# vco1_pots.net
KiCad netlist of a schematic drawn in EAGLE
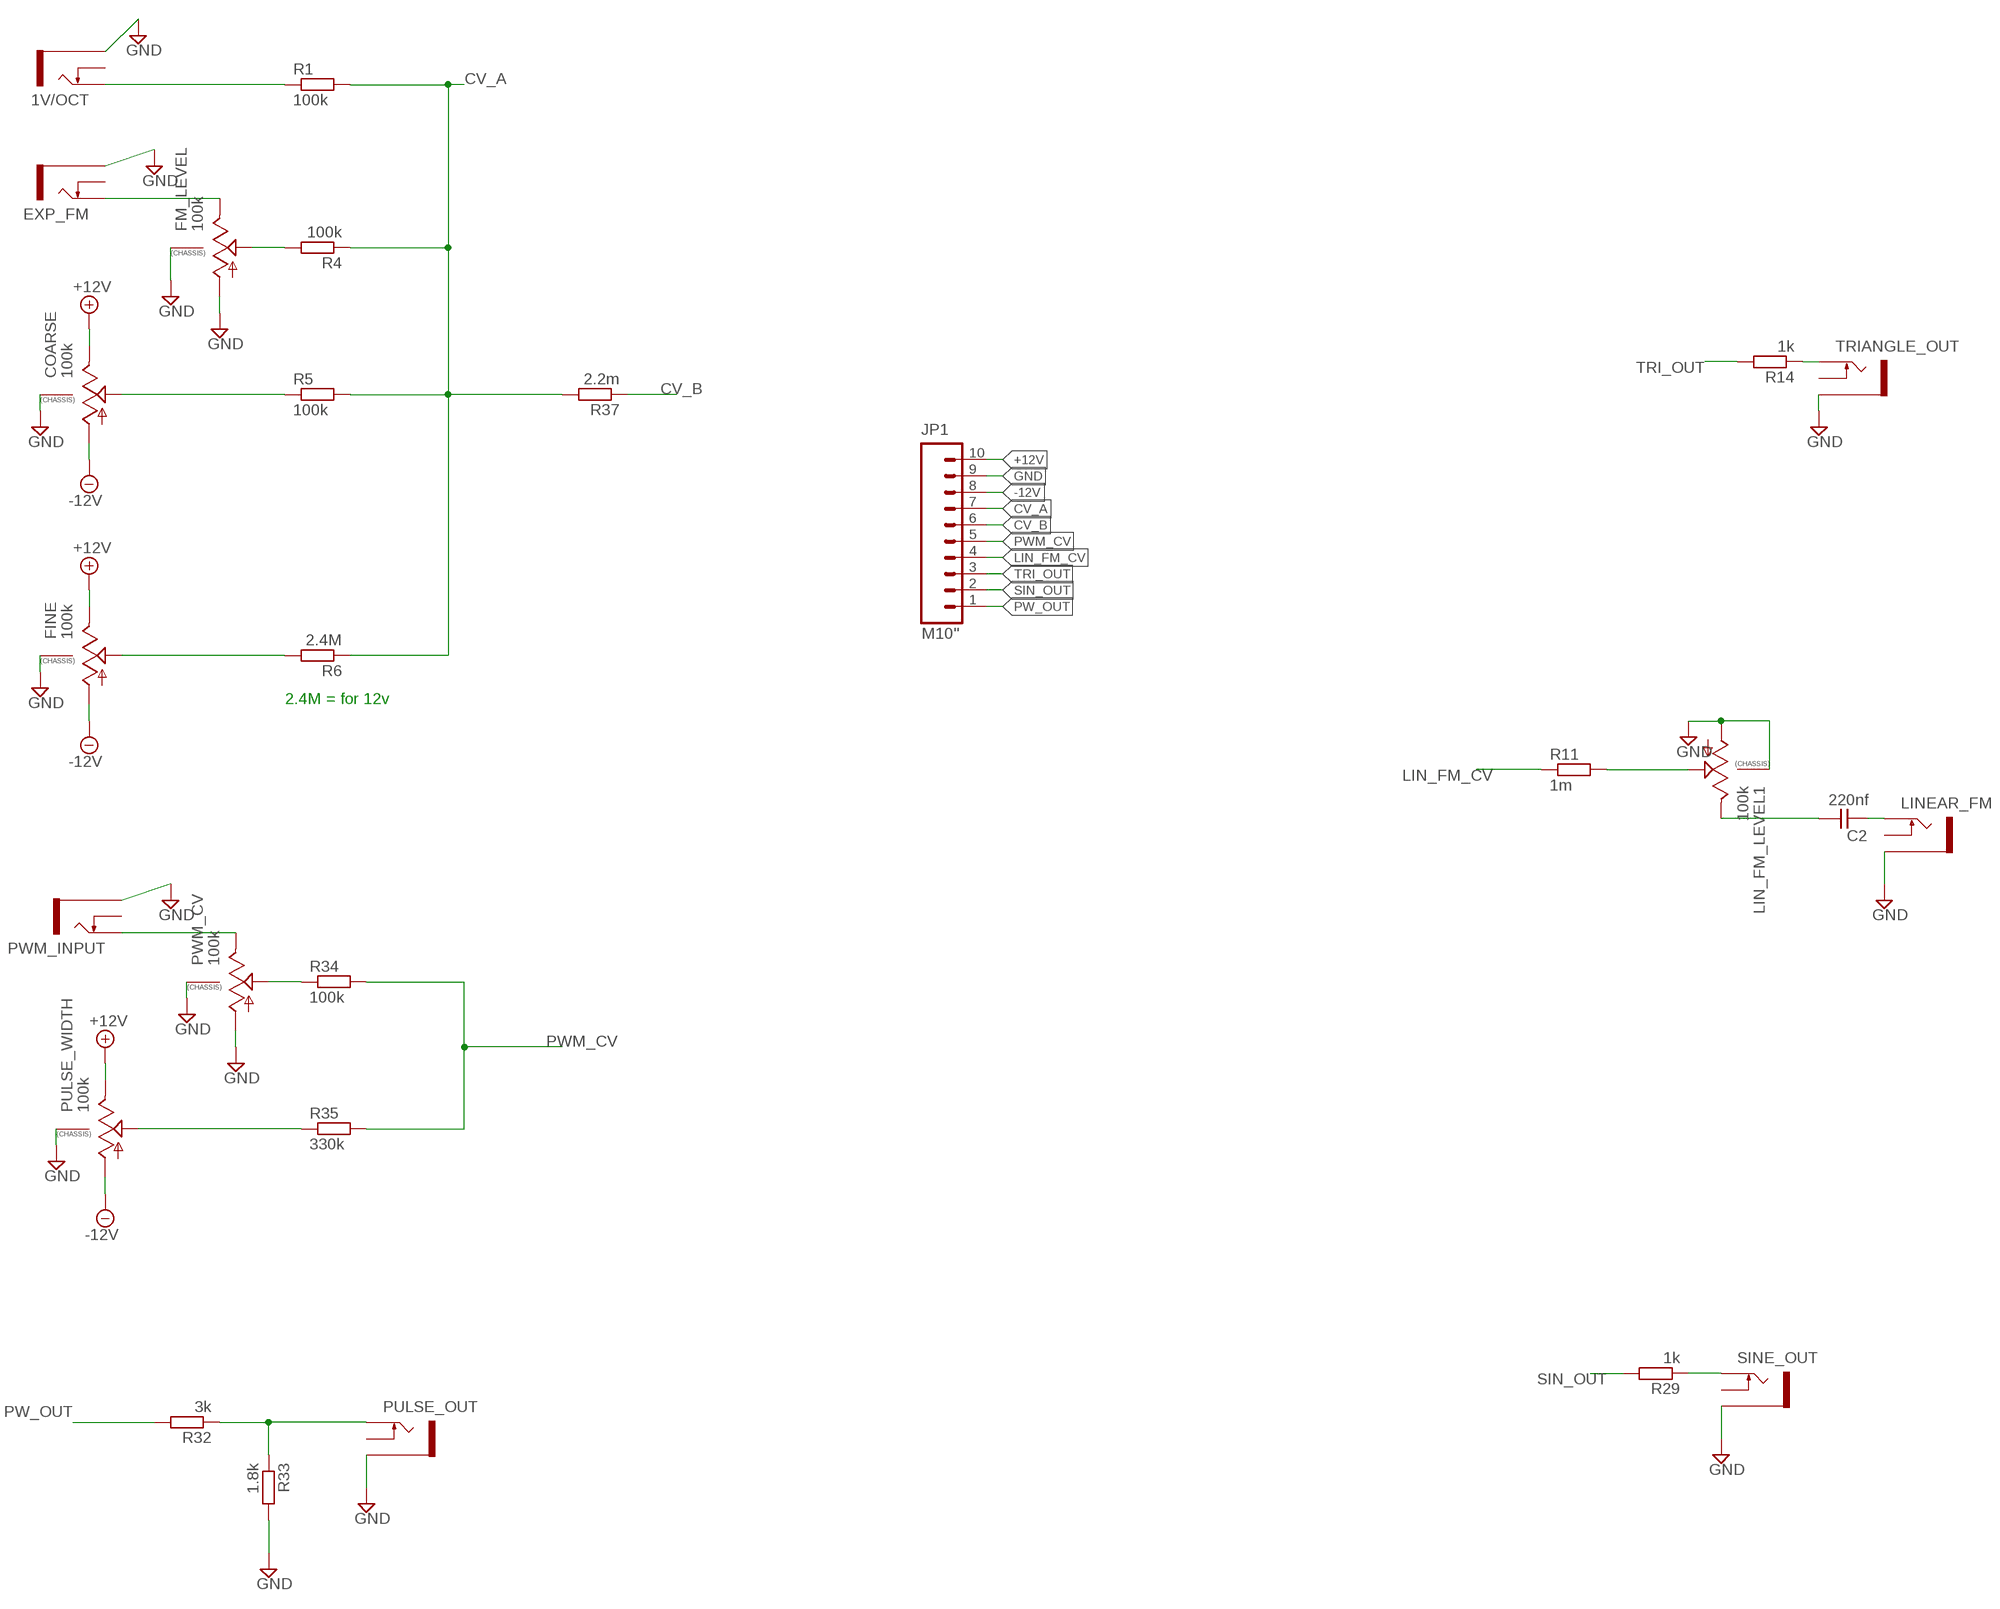
[diagram p0: schematic, sheet 1]

(export (version "E")
  (design (tool "Eeschema 10.0.6"))
  (components
    (comp (ref "1V/OCT")
      (value "THONKICONNNEW")
      (footprint "eagle-import:WQP-PJ301M-12_JACK")
      (libsource (lib "eagle-import") (part "THONKICONNNEW"))
    )
    (comp (ref "C2")
      (value "220nf")
      (footprint "eagle-import:C050-024X044")
      (libsource (lib "eagle-import") (part "C-EU050-024X044"))
    )
    (comp (ref "COARSE")
      (value "100k")
      (footprint "eagle-import:9MM_SNAP-IN_POT")
      (libsource (lib "eagle-import") (part "9MM_SNAP-IN_POT_CHASSIS"))
    )
    (comp (ref "EXP_FM")
      (value "THONKICONNNEW")
      (footprint "eagle-import:WQP-PJ301M-12_JACK")
      (libsource (lib "eagle-import") (part "THONKICONNNEW"))
    )
    (comp (ref "FINE")
      (value "100k")
      (footprint "eagle-import:9MM_SNAP-IN_POT")
      (libsource (lib "eagle-import") (part "9MM_SNAP-IN_POT_CHASSIS"))
    )
    (comp (ref "FM_LEVEL")
      (value "100k")
      (footprint "eagle-import:9MM_SNAP-IN_POT")
      (libsource (lib "eagle-import") (part "9MM_SNAP-IN_POT_CHASSIS"))
    )
    (comp (ref "JP1")
      (value "M10\"")
      (footprint "eagle-import:1X10")
      (libsource (lib "eagle-import") (part "M10{dblquote}"))
    )
    (comp (ref "LINEAR_FM")
      (value "THONKICONNNEW")
      (footprint "eagle-import:WQP-PJ301M-12_JACK")
      (libsource (lib "eagle-import") (part "THONKICONNNEW"))
    )
    (comp (ref "LIN_FM_LEVEL1")
      (value "100k")
      (footprint "eagle-import:9MM_SNAP-IN_POT")
      (libsource (lib "eagle-import") (part "9MM_SNAP-IN_POT_CHASSIS"))
    )
    (comp (ref "PULSE_OUT")
      (value "THONKICONNNEW")
      (footprint "eagle-import:WQP-PJ301M-12_JACK")
      (libsource (lib "eagle-import") (part "THONKICONNNEW"))
    )
    (comp (ref "PULSE_WIDTH")
      (value "100k")
      (footprint "eagle-import:9MM_SNAP-IN_POT")
      (libsource (lib "eagle-import") (part "9MM_SNAP-IN_POT_CHASSIS"))
    )
    (comp (ref "PWM_CV")
      (value "100k")
      (footprint "eagle-import:9MM_SNAP-IN_POT")
      (libsource (lib "eagle-import") (part "9MM_SNAP-IN_POT_CHASSIS"))
    )
    (comp (ref "PWM_INPUT")
      (value "THONKICONNNEW")
      (footprint "eagle-import:WQP-PJ301M-12_JACK")
      (libsource (lib "eagle-import") (part "THONKICONNNEW"))
    )
    (comp (ref "R1")
      (value "100k")
      (footprint "eagle-import:7MM_RESISTOR")
      (libsource (lib "eagle-import") (part "RESISTOR7MM"))
    )
    (comp (ref "R4")
      (value "100k")
      (footprint "eagle-import:7MM_RESISTOR")
      (libsource (lib "eagle-import") (part "RESISTOR7MM"))
    )
    (comp (ref "R5")
      (value "100k")
      (footprint "eagle-import:7MM_RESISTOR")
      (libsource (lib "eagle-import") (part "RESISTOR7MM"))
    )
    (comp (ref "R6")
      (value "2.4M")
      (footprint "eagle-import:7MM_RESISTOR")
      (libsource (lib "eagle-import") (part "RESISTOR7MM"))
    )
    (comp (ref "R11")
      (value "1m")
      (footprint "eagle-import:7MM_RESISTOR")
      (libsource (lib "eagle-import") (part "RESISTOR7MM"))
    )
    (comp (ref "R14")
      (value "1k")
      (footprint "eagle-import:7MM_RESISTOR")
      (libsource (lib "eagle-import") (part "RESISTOR7MM"))
    )
    (comp (ref "R29")
      (value "1k")
      (footprint "eagle-import:7MM_RESISTOR")
      (libsource (lib "eagle-import") (part "RESISTOR7MM"))
    )
    (comp (ref "R32")
      (value "3k")
      (footprint "eagle-import:7MM_RESISTOR")
      (libsource (lib "eagle-import") (part "RESISTOR7MM"))
    )
    (comp (ref "R33")
      (value "1.8k")
      (footprint "eagle-import:7MM_RESISTOR")
      (libsource (lib "eagle-import") (part "RESISTOR7MM"))
    )
    (comp (ref "R34")
      (value "100k")
      (footprint "eagle-import:7MM_RESISTOR")
      (libsource (lib "eagle-import") (part "RESISTOR7MM"))
    )
    (comp (ref "R35")
      (value "330k")
      (footprint "eagle-import:7MM_RESISTOR")
      (libsource (lib "eagle-import") (part "RESISTOR7MM"))
    )
    (comp (ref "R37")
      (value "2.2m")
      (footprint "eagle-import:7MM_RESISTOR")
      (libsource (lib "eagle-import") (part "RESISTOR7MM"))
    )
    (comp (ref "SINE_OUT")
      (value "THONKICONNNEW")
      (footprint "eagle-import:WQP-PJ301M-12_JACK")
      (libsource (lib "eagle-import") (part "THONKICONNNEW"))
    )
    (comp (ref "TRIANGLE_OUT")
      (value "THONKICONNNEW")
      (footprint "eagle-import:WQP-PJ301M-12_JACK")
      (libsource (lib "eagle-import") (part "THONKICONNNEW"))
    )
  )
  (nets
    (net (code "1") (name "+12V") (class "Default")
      (node (ref "COARSE") (pin "3") (pinfunction "E_3") (pintype "passive"))
      (node (ref "FINE") (pin "3") (pinfunction "E_3") (pintype "passive"))
      (node (ref "JP1") (pin "10") (pinfunction "10_10") (pintype "passive"))
      (node (ref "PULSE_WIDTH") (pin "3") (pinfunction "E_3") (pintype "passive"))
    )
    (net (code "2") (name "-12V") (class "Default")
      (node (ref "COARSE") (pin "1") (pinfunction "A_1") (pintype "passive"))
      (node (ref "FINE") (pin "1") (pinfunction "A_1") (pintype "passive"))
      (node (ref "JP1") (pin "8") (pinfunction "8_8") (pintype "passive"))
      (node (ref "PULSE_WIDTH") (pin "1") (pinfunction "A_1") (pintype "passive"))
    )
    (net (code "3") (name "CV_A") (class "Default")
      (node (ref "JP1") (pin "7") (pinfunction "7_7") (pintype "passive"))
      (node (ref "R1") (pin "2") (pinfunction "2_2") (pintype "passive"))
      (node (ref "R37") (pin "2") (pinfunction "2_2") (pintype "passive"))
      (node (ref "R4") (pin "1") (pinfunction "1_1") (pintype "passive"))
      (node (ref "R5") (pin "2") (pinfunction "2_2") (pintype "passive"))
      (node (ref "R6") (pin "1") (pinfunction "1_1") (pintype "passive"))
    )
    (net (code "4") (name "CV_B") (class "Default")
      (node (ref "JP1") (pin "6") (pinfunction "6_6") (pintype "passive"))
      (node (ref "R37") (pin "1") (pinfunction "1_1") (pintype "passive"))
    )
    (net (code "5") (name "GND") (class "Default")
      (node (ref "1V/OCT") (pin "P$3_SLEEVE") (pinfunction "SLEEVE_P$3_SLEEVE") (pintype "passive"))
      (node (ref "COARSE") (pin "CHASSIS2") (pinfunction "P$1_CHASSIS2") (pintype "passive"))
      (node (ref "EXP_FM") (pin "P$3_SLEEVE") (pinfunction "SLEEVE_P$3_SLEEVE") (pintype "passive"))
      (node (ref "FINE") (pin "CHASSIS2") (pinfunction "P$1_CHASSIS2") (pintype "passive"))
      (node (ref "FM_LEVEL") (pin "1") (pinfunction "A_1") (pintype "passive"))
      (node (ref "FM_LEVEL") (pin "CHASSIS2") (pinfunction "P$1_CHASSIS2") (pintype "passive"))
      (node (ref "JP1") (pin "9") (pinfunction "9_9") (pintype "passive"))
      (node (ref "LINEAR_FM") (pin "P$3_SLEEVE") (pinfunction "SLEEVE_P$3_SLEEVE") (pintype "passive"))
      (node (ref "LIN_FM_LEVEL1") (pin "1") (pinfunction "A_1") (pintype "passive"))
      (node (ref "LIN_FM_LEVEL1") (pin "CHASSIS2") (pinfunction "P$1_CHASSIS2") (pintype "passive"))
      (node (ref "PULSE_OUT") (pin "P$3_SLEEVE") (pinfunction "SLEEVE_P$3_SLEEVE") (pintype "passive"))
      (node (ref "PULSE_WIDTH") (pin "CHASSIS2") (pinfunction "P$1_CHASSIS2") (pintype "passive"))
      (node (ref "PWM_CV") (pin "1") (pinfunction "A_1") (pintype "passive"))
      (node (ref "PWM_CV") (pin "CHASSIS2") (pinfunction "P$1_CHASSIS2") (pintype "passive"))
      (node (ref "PWM_INPUT") (pin "P$3_SLEEVE") (pinfunction "SLEEVE_P$3_SLEEVE") (pintype "passive"))
      (node (ref "R33") (pin "2") (pinfunction "2_2") (pintype "passive"))
      (node (ref "SINE_OUT") (pin "P$3_SLEEVE") (pinfunction "SLEEVE_P$3_SLEEVE") (pintype "passive"))
      (node (ref "TRIANGLE_OUT") (pin "P$3_SLEEVE") (pinfunction "SLEEVE_P$3_SLEEVE") (pintype "passive"))
    )
    (net (code "6") (name "LIN_FM_CV") (class "Default")
      (node (ref "JP1") (pin "4") (pinfunction "4_4") (pintype "passive"))
      (node (ref "R11") (pin "1") (pinfunction "1_1") (pintype "passive"))
    )
    (net (code "7") (name "Net-(1V/OCT-TIP)") (class "Default")
      (node (ref "1V/OCT") (pin "P$1_TIP") (pinfunction "TIP_P$1_TIP") (pintype "passive"))
      (node (ref "R1") (pin "1") (pinfunction "1_1") (pintype "passive"))
    )
    (net (code "8") (name "Net-(COARSE-S)") (class "Default")
      (node (ref "COARSE") (pin "2") (pinfunction "S_2") (pintype "passive"))
      (node (ref "R5") (pin "1") (pinfunction "1_1") (pintype "passive"))
    )
    (net (code "9") (name "Net-(EXP_FM-TIP)") (class "Default")
      (node (ref "EXP_FM") (pin "P$1_TIP") (pinfunction "TIP_P$1_TIP") (pintype "passive"))
      (node (ref "FM_LEVEL") (pin "3") (pinfunction "E_3") (pintype "passive"))
    )
    (net (code "10") (name "Net-(FINE-S)") (class "Default")
      (node (ref "FINE") (pin "2") (pinfunction "S_2") (pintype "passive"))
      (node (ref "R6") (pin "2") (pinfunction "2_2") (pintype "passive"))
    )
    (net (code "11") (name "Net-(FM_LEVEL-S)") (class "Default")
      (node (ref "FM_LEVEL") (pin "2") (pinfunction "S_2") (pintype "passive"))
      (node (ref "R4") (pin "2") (pinfunction "2_2") (pintype "passive"))
    )
    (net (code "12") (name "Net-(LINEAR_FM-TIP)") (class "Default")
      (node (ref "C2") (pin "2") (pinfunction "2_2") (pintype "passive"))
      (node (ref "LINEAR_FM") (pin "P$1_TIP") (pinfunction "TIP_P$1_TIP") (pintype "passive"))
    )
    (net (code "13") (name "Net-(LIN_FM_LEVEL1-E)") (class "Default")
      (node (ref "C2") (pin "1") (pinfunction "1_1") (pintype "passive"))
      (node (ref "LIN_FM_LEVEL1") (pin "3") (pinfunction "E_3") (pintype "passive"))
    )
    (net (code "14") (name "Net-(LIN_FM_LEVEL1-S)") (class "Default")
      (node (ref "LIN_FM_LEVEL1") (pin "2") (pinfunction "S_2") (pintype "passive"))
      (node (ref "R11") (pin "2") (pinfunction "2_2") (pintype "passive"))
    )
    (net (code "15") (name "Net-(PULSE_OUT-TIP)") (class "Default")
      (node (ref "PULSE_OUT") (pin "P$1_TIP") (pinfunction "TIP_P$1_TIP") (pintype "passive"))
      (node (ref "R32") (pin "1") (pinfunction "1_1") (pintype "passive"))
      (node (ref "R33") (pin "1") (pinfunction "1_1") (pintype "passive"))
    )
    (net (code "16") (name "Net-(PULSE_WIDTH-S)") (class "Default")
      (node (ref "PULSE_WIDTH") (pin "2") (pinfunction "S_2") (pintype "passive"))
      (node (ref "R35") (pin "1") (pinfunction "1_1") (pintype "passive"))
    )
    (net (code "17") (name "Net-(PWM_CV-E)") (class "Default")
      (node (ref "PWM_CV") (pin "3") (pinfunction "E_3") (pintype "passive"))
      (node (ref "PWM_INPUT") (pin "P$1_TIP") (pinfunction "TIP_P$1_TIP") (pintype "passive"))
    )
    (net (code "18") (name "Net-(PWM_CV-S)") (class "Default")
      (node (ref "PWM_CV") (pin "2") (pinfunction "S_2") (pintype "passive"))
      (node (ref "R34") (pin "1") (pinfunction "1_1") (pintype "passive"))
    )
    (net (code "19") (name "Net-(SINE_OUT-TIP)") (class "Default")
      (node (ref "R29") (pin "1") (pinfunction "1_1") (pintype "passive"))
      (node (ref "SINE_OUT") (pin "P$1_TIP") (pinfunction "TIP_P$1_TIP") (pintype "passive"))
    )
    (net (code "20") (name "Net-(TRIANGLE_OUT-TIP)") (class "Default")
      (node (ref "R14") (pin "1") (pinfunction "1_1") (pintype "passive"))
      (node (ref "TRIANGLE_OUT") (pin "P$1_TIP") (pinfunction "TIP_P$1_TIP") (pintype "passive"))
    )
    (net (code "21") (name "PWM_CV") (class "Default")
      (node (ref "JP1") (pin "5") (pinfunction "5_5") (pintype "passive"))
      (node (ref "R34") (pin "2") (pinfunction "2_2") (pintype "passive"))
      (node (ref "R35") (pin "2") (pinfunction "2_2") (pintype "passive"))
    )
    (net (code "22") (name "PW_OUT") (class "Default")
      (node (ref "JP1") (pin "1") (pinfunction "1_1") (pintype "passive"))
      (node (ref "R32") (pin "2") (pinfunction "2_2") (pintype "passive"))
    )
    (net (code "23") (name "SIN_OUT") (class "Default")
      (node (ref "JP1") (pin "2") (pinfunction "2_2") (pintype "passive"))
      (node (ref "R29") (pin "2") (pinfunction "2_2") (pintype "passive"))
    )
    (net (code "24") (name "TRI_OUT") (class "Default")
      (node (ref "JP1") (pin "3") (pinfunction "3_3") (pintype "passive"))
      (node (ref "R14") (pin "2") (pinfunction "2_2") (pintype "passive"))
    )
    (net (code "25") (name "unconnected-(1V/OCT-SWITCH-PadP$2_SWITCH)") (class "Default")
      (node (ref "1V/OCT") (pin "P$2_SWITCH") (pinfunction "SWITCH_P$2_SWITCH") (pintype "passive"))
    )
    (net (code "26") (name "unconnected-(EXP_FM-SWITCH-PadP$2_SWITCH)") (class "Default")
      (node (ref "EXP_FM") (pin "P$2_SWITCH") (pinfunction "SWITCH_P$2_SWITCH") (pintype "passive"))
    )
    (net (code "27") (name "unconnected-(LINEAR_FM-SWITCH-PadP$2_SWITCH)") (class "Default")
      (node (ref "LINEAR_FM") (pin "P$2_SWITCH") (pinfunction "SWITCH_P$2_SWITCH") (pintype "passive"))
    )
    (net (code "28") (name "unconnected-(PULSE_OUT-SWITCH-PadP$2_SWITCH)") (class "Default")
      (node (ref "PULSE_OUT") (pin "P$2_SWITCH") (pinfunction "SWITCH_P$2_SWITCH") (pintype "passive"))
    )
    (net (code "29") (name "unconnected-(PWM_INPUT-SWITCH-PadP$2_SWITCH)") (class "Default")
      (node (ref "PWM_INPUT") (pin "P$2_SWITCH") (pinfunction "SWITCH_P$2_SWITCH") (pintype "passive"))
    )
    (net (code "30") (name "unconnected-(SINE_OUT-SWITCH-PadP$2_SWITCH)") (class "Default")
      (node (ref "SINE_OUT") (pin "P$2_SWITCH") (pinfunction "SWITCH_P$2_SWITCH") (pintype "passive"))
    )
    (net (code "31") (name "unconnected-(TRIANGLE_OUT-SWITCH-PadP$2_SWITCH)") (class "Default")
      (node (ref "TRIANGLE_OUT") (pin "P$2_SWITCH") (pinfunction "SWITCH_P$2_SWITCH") (pintype "passive"))
    )
  )
)
